# Page_A_Power.net
KiCad netlist of a schematic drawn in Altium Designer
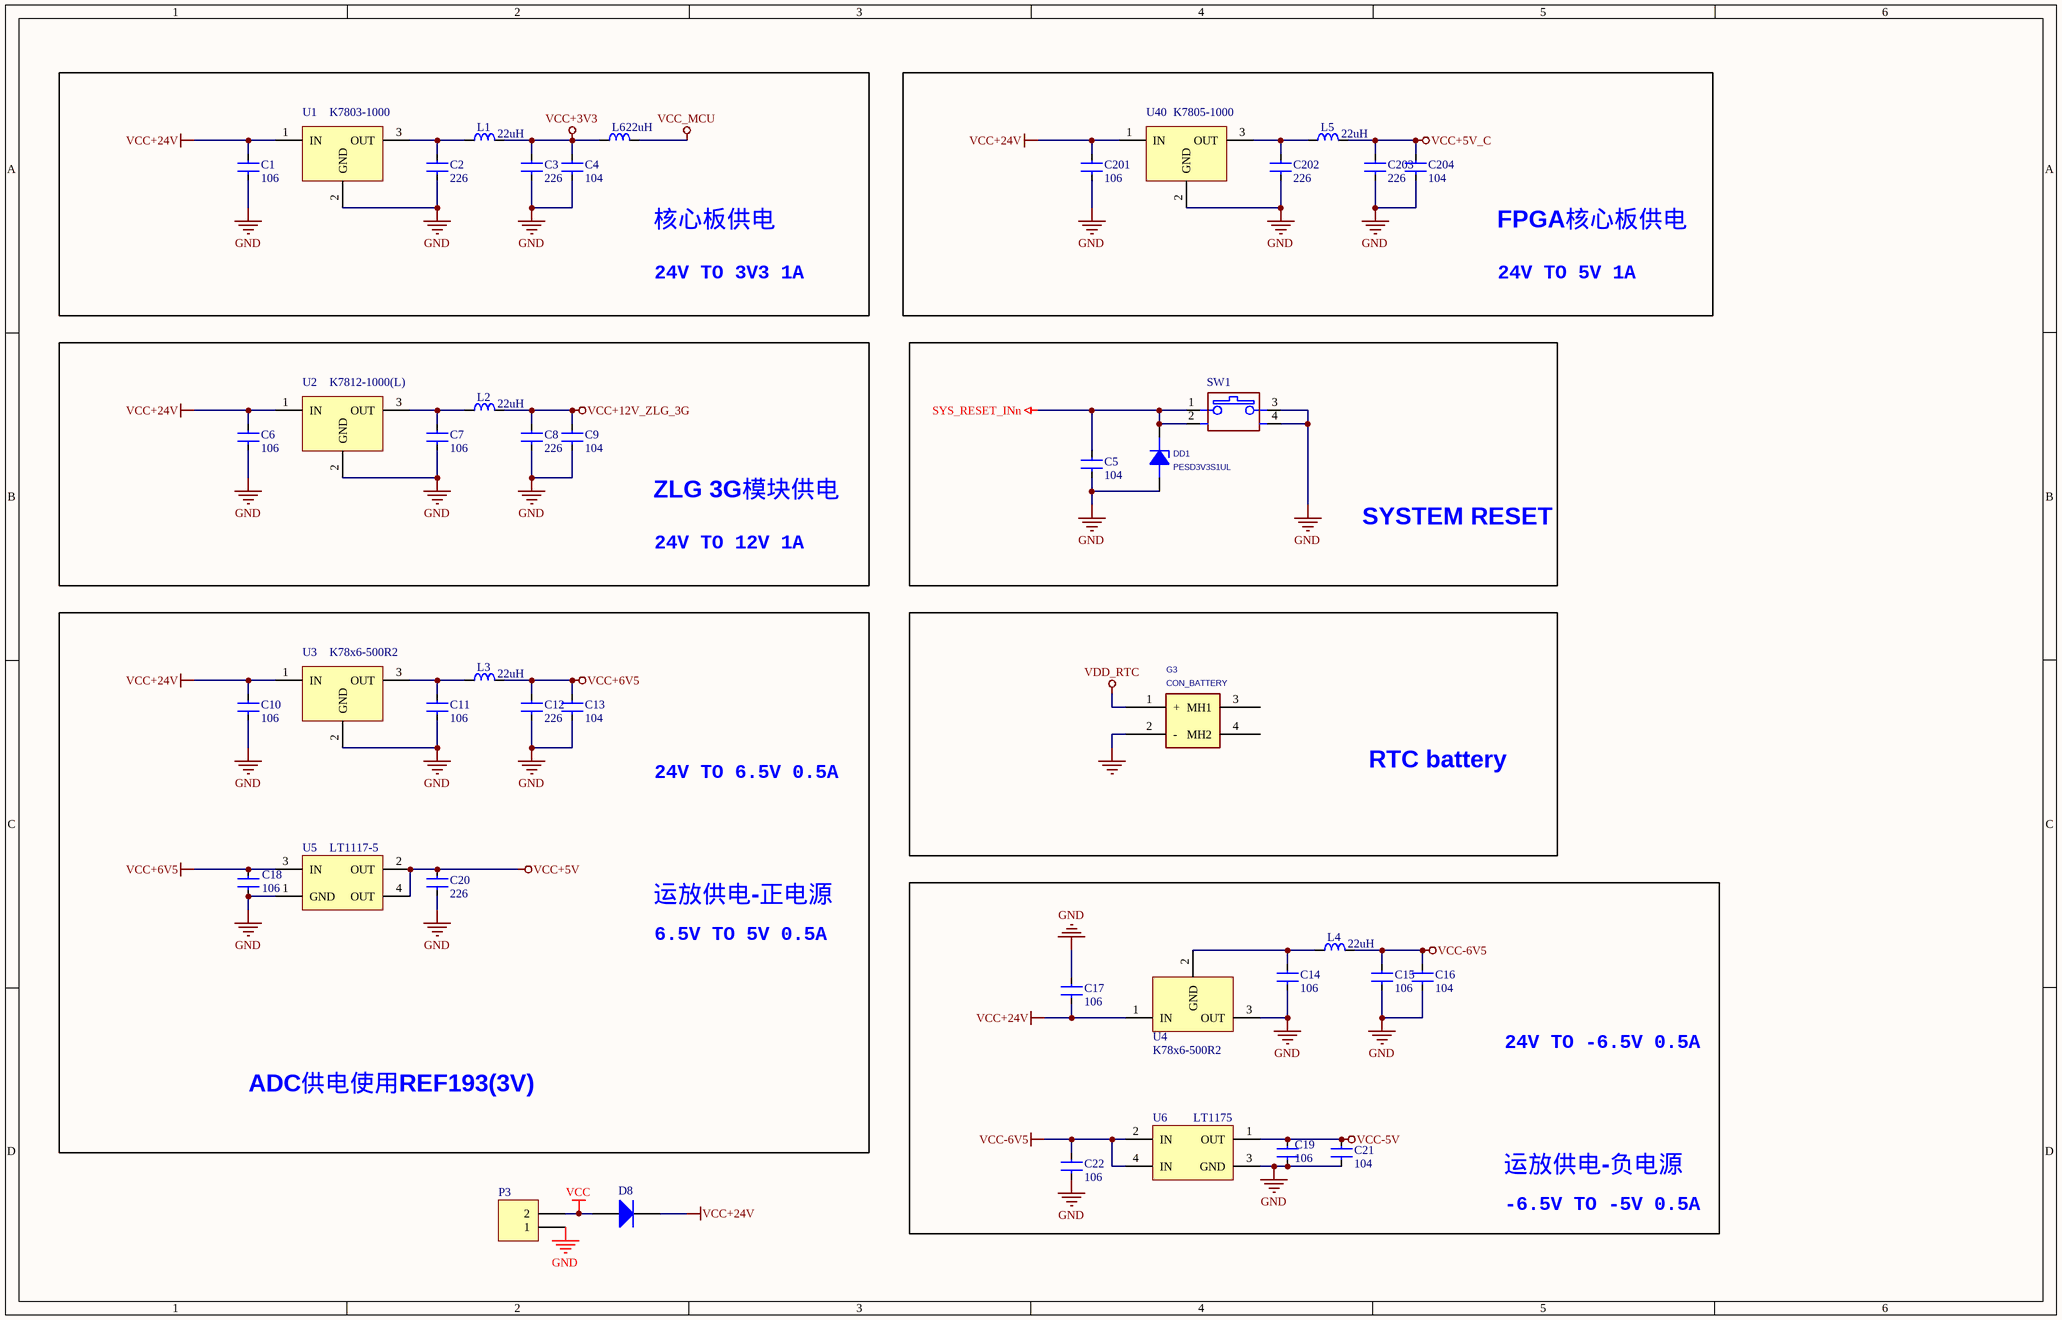
[diagram p0: Page A_Power.SchDoc]

(export (version "E")
  (design (tool "Eeschema 10.0.6"))
  (components
    (comp (ref "C1")
      (value "106")
      (footprint "0805C")
      (description "SMD")
      (libsource (lib "无极性电容") (part "C-SMD"))
    )
    (comp (ref "C2")
      (value "226")
      (footprint "0805C")
      (description "SMD")
      (libsource (lib "无极性电容") (part "C-SMD"))
    )
    (comp (ref "C3")
      (value "226")
      (footprint "0805C")
      (description "SMD")
      (libsource (lib "无极性电容") (part "C-SMD"))
    )
    (comp (ref "C4")
      (value "104")
      (footprint "0805C")
      (description "SMD")
      (libsource (lib "无极性电容") (part "C-SMD"))
    )
    (comp (ref "C5")
      (value "104")
      (footprint "0805C")
      (description "SMD")
      (libsource (lib "无极性电容") (part "C-SMD"))
    )
    (comp (ref "C6")
      (value "106")
      (footprint "0805C")
      (description "SMD")
      (libsource (lib "无极性电容") (part "C-SMD"))
    )
    (comp (ref "C7")
      (value "106")
      (footprint "0805C")
      (description "SMD")
      (libsource (lib "无极性电容") (part "C-SMD"))
    )
    (comp (ref "C8")
      (value "226")
      (footprint "0805C")
      (description "SMD")
      (libsource (lib "无极性电容") (part "C-SMD"))
    )
    (comp (ref "C9")
      (value "104")
      (footprint "0805C")
      (description "SMD")
      (libsource (lib "无极性电容") (part "C-SMD"))
    )
    (comp (ref "C10")
      (value "106")
      (footprint "0805C")
      (description "SMD")
      (libsource (lib "无极性电容") (part "C-SMD"))
    )
    (comp (ref "C11")
      (value "106")
      (footprint "0805C")
      (description "SMD")
      (libsource (lib "无极性电容") (part "C-SMD"))
    )
    (comp (ref "C12")
      (value "226")
      (footprint "0805C")
      (description "SMD")
      (libsource (lib "无极性电容") (part "C-SMD"))
    )
    (comp (ref "C13")
      (value "104")
      (footprint "0805C")
      (description "SMD")
      (libsource (lib "无极性电容") (part "C-SMD"))
    )
    (comp (ref "C14")
      (value "106")
      (footprint "0805C")
      (description "SMD")
      (libsource (lib "无极性电容") (part "C-SMD"))
    )
    (comp (ref "C15")
      (value "106")
      (footprint "0805C")
      (description "SMD")
      (libsource (lib "无极性电容") (part "C-SMD"))
    )
    (comp (ref "C16")
      (value "104")
      (footprint "0805C")
      (description "SMD")
      (libsource (lib "无极性电容") (part "C-SMD"))
    )
    (comp (ref "C17")
      (value "106")
      (footprint "0805C")
      (description "SMD")
      (libsource (lib "无极性电容") (part "C-SMD"))
    )
    (comp (ref "C18")
      (value "106")
      (footprint "0805C")
      (description "SMD")
      (libsource (lib "无极性电容") (part "C-SMD"))
    )
    (comp (ref "C19")
      (value "106")
      (footprint "0805C")
      (description "C-X5R/X7R")
      (libsource (lib "贴片电阻电容") (part "C-X5R/X7R"))
    )
    (comp (ref "C20")
      (value "226")
      (footprint "0805C")
      (description "SMD")
      (libsource (lib "无极性电容") (part "C-SMD"))
    )
    (comp (ref "C21")
      (value "104")
      (footprint "0805C")
      (description "C-X5R/X7R")
      (libsource (lib "贴片电阻电容") (part "C-X5R/X7R"))
    )
    (comp (ref "C22")
      (value "106")
      (footprint "0805C")
      (description "C-X5R/X7R")
      (libsource (lib "贴片电阻电容") (part "C-X5R/X7R"))
    )
    (comp (ref "C201")
      (value "106")
      (footprint "0805C")
      (description "SMD")
      (libsource (lib "无极性电容") (part "C-SMD"))
    )
    (comp (ref "C202")
      (value "226")
      (footprint "0805C")
      (description "SMD")
      (libsource (lib "无极性电容") (part "C-SMD"))
    )
    (comp (ref "C203")
      (value "226")
      (footprint "0805C")
      (description "SMD")
      (libsource (lib "无极性电容") (part "C-SMD"))
    )
    (comp (ref "C204")
      (value "104")
      (footprint "0805C")
      (description "SMD")
      (libsource (lib "无极性电容") (part "C-SMD"))
    )
    (comp (ref "D8")
      (value "1N4007")
      (footprint "DO-41")
      (description "High Conductance Fast Diode")
      (fields (field (name "PUBLISHER") "Altium Limited"))
      (libsource (lib "Miscellaneous Devices") (part "Diode 1N4148"))
    )
    (comp (ref "DD1")
      (value "PESD3V3S1UL")
      (footprint "SOD882")
      (fields (field (name "MANUFACTURER") "NXP"))
      (libsource (lib "*") (part "DIODE BREAKDOWN"))
    )
    (comp (ref "G3")
      (value "CON_BATTERY")
      (footprint "CON_BATTERY_CR1220")
      (libsource (lib "*") (part "CON_BATTERY"))
    )
    (comp (ref "L1")
      (value "22uH")
      (footprint "1210")
      (description "Inductor")
      (fields
        (field (name "PART NUMBER") "IND0603_TDK_MPZ1608R391A")
        (field (name "POWER") "1.2A")
        (field (name "AUTHOR") "CERN DEM JLC")
      )
      (libsource (lib "电感、变压器件") (part "Inductor"))
    )
    (comp (ref "L2")
      (value "22uH")
      (footprint "1210")
      (description "Inductor")
      (fields
        (field (name "PART NUMBER") "IND0603_TDK_MPZ1608R391A")
        (field (name "POWER") "1.2A")
        (field (name "AUTHOR") "CERN DEM JLC")
      )
      (libsource (lib "电感、变压器件") (part "Inductor"))
    )
    (comp (ref "L3")
      (value "22uH")
      (footprint "1210")
      (description "Inductor")
      (fields
        (field (name "PART NUMBER") "IND0603_TDK_MPZ1608R391A")
        (field (name "POWER") "1.2A")
        (field (name "AUTHOR") "CERN DEM JLC")
      )
      (libsource (lib "电感、变压器件") (part "Inductor"))
    )
    (comp (ref "L4")
      (value "22uH")
      (footprint "1210")
      (description "Inductor")
      (fields
        (field (name "PART NUMBER") "IND0603_TDK_MPZ1608R391A")
        (field (name "POWER") "1.2A")
        (field (name "AUTHOR") "CERN DEM JLC")
      )
      (libsource (lib "电感、变压器件") (part "Inductor"))
    )
    (comp (ref "L5")
      (value "22uH")
      (footprint "1210")
      (description "Inductor")
      (fields
        (field (name "PART NUMBER") "IND0603_TDK_MPZ1608R391A")
        (field (name "POWER") "1.2A")
        (field (name "AUTHOR") "CERN DEM JLC")
      )
      (libsource (lib "电感、变压器件") (part "Inductor"))
    )
    (comp (ref "L6")
      (value "22uH")
      (footprint "1210")
      (description "Inductor")
      (fields
        (field (name "PART NUMBER") "IND0603_TDK_MPZ1608R391A")
        (field (name "POWER") "1.2A")
        (field (name "AUTHOR") "CERN DEM JLC")
      )
      (libsource (lib "电感、变压器件") (part "Inductor"))
    )
    (comp (ref "P3")
      (value "Header 2")
      (footprint "7.62-2P")
      (description "Header, 2-Pin")
      (fields (field (name "PUBLISHER") "Altium Limited"))
      (libsource (lib "Miscellaneous Connectors") (part "Header 2"))
    )
    (comp (ref "SW1")
      (value "SW PUSHBUTTON-SPST SHIELD_0")
      (footprint "BUTTON_SW_SMD_4P_BIG")
      (libsource (lib "TL138_1808_6748F-EASYEVM-A2_Library") (part "SW PUSHBUTTON-SPST SHIELD_0"))
    )
    (comp (ref "U1")
      (value "K7803-1000")
      (footprint "K78xx-500R2")
      (description "K78xx-500R2")
      (libsource (lib "其他元器件") (part "K78xx-500R2"))
    )
    (comp (ref "U2")
      (value "K7812-1000(L)")
      (footprint "K78xx-L")
      (description "K78xx-500R2")
      (libsource (lib "其他元器件") (part "K78xx-500R2"))
    )
    (comp (ref "U3")
      (value "K78x6-500R2")
      (footprint "K78xx-500R2")
      (description "K78xx-500R2")
      (libsource (lib "其他元器件") (part "K78xx-500R2"))
    )
    (comp (ref "U4")
      (value "K78x6-500R2")
      (footprint "K78xx-500R2")
      (description "K78xx-500R2")
      (libsource (lib "") (part "K78xx-500R2_1"))
    )
    (comp (ref "U5")
      (value "LT1117-5")
      (footprint "SOT-223")
      (description "AMS1117")
      (libsource (lib "其他元器件") (part "AMS1117"))
    )
    (comp (ref "U6") (value "LT1175") (footprint "SOT-223") (libsource (lib "其他元器件") (part "LT1175")))
    (comp (ref "U40")
      (value "K7805-1000")
      (footprint "K78xx-500R2")
      (description "K78xx-500R2")
      (libsource (lib "其他元器件") (part "K78xx-500R2"))
    )
  )
  (nets
    (net (code "1") (name "GND") (class "Default")
      (node (ref "C1") (pin "2") (pinfunction "2_2") (pintype "passive"))
      (node (ref "C10") (pin "2") (pinfunction "2_2") (pintype "passive"))
      (node (ref "C11") (pin "2") (pinfunction "2_2") (pintype "passive"))
      (node (ref "C12") (pin "2") (pinfunction "2_2") (pintype "passive"))
      (node (ref "C13") (pin "2") (pinfunction "2_2") (pintype "passive"))
      (node (ref "C14") (pin "2") (pinfunction "2_2") (pintype "passive"))
      (node (ref "C15") (pin "2") (pinfunction "2_2") (pintype "passive"))
      (node (ref "C16") (pin "2") (pinfunction "2_2") (pintype "passive"))
      (node (ref "C17") (pin "2") (pinfunction "2_2") (pintype "passive"))
      (node (ref "C18") (pin "2") (pinfunction "2_2") (pintype "passive"))
      (node (ref "C19") (pin "2") (pinfunction "2_2") (pintype "passive"))
      (node (ref "C2") (pin "2") (pinfunction "2_2") (pintype "passive"))
      (node (ref "C20") (pin "2") (pinfunction "2_2") (pintype "passive"))
      (node (ref "C201") (pin "2") (pinfunction "2_2") (pintype "passive"))
      (node (ref "C202") (pin "2") (pinfunction "2_2") (pintype "passive"))
      (node (ref "C203") (pin "2") (pinfunction "2_2") (pintype "passive"))
      (node (ref "C204") (pin "2") (pinfunction "2_2") (pintype "passive"))
      (node (ref "C21") (pin "2") (pinfunction "2_2") (pintype "passive"))
      (node (ref "C22") (pin "2") (pinfunction "2_2") (pintype "passive"))
      (node (ref "C3") (pin "2") (pinfunction "2_2") (pintype "passive"))
      (node (ref "C4") (pin "2") (pinfunction "2_2") (pintype "passive"))
      (node (ref "C5") (pin "2") (pinfunction "2_2") (pintype "passive"))
      (node (ref "C6") (pin "2") (pinfunction "2_2") (pintype "passive"))
      (node (ref "C7") (pin "2") (pinfunction "2_2") (pintype "passive"))
      (node (ref "C8") (pin "2") (pinfunction "2_2") (pintype "passive"))
      (node (ref "C9") (pin "2") (pinfunction "2_2") (pintype "passive"))
      (node (ref "DD1") (pin "2") (pinfunction "ANODE_2") (pintype "passive"))
      (node (ref "G3") (pin "2") (pinfunction "-_2") (pintype "passive"))
      (node (ref "P3") (pin "1") (pinfunction "1_1") (pintype "passive"))
      (node (ref "SW1") (pin "3") (pinfunction "3_3") (pintype "passive"))
      (node (ref "SW1") (pin "4") (pinfunction "4_4") (pintype "passive"))
      (node (ref "U1") (pin "2") (pinfunction "GND_2") (pintype "passive"))
      (node (ref "U2") (pin "2") (pinfunction "GND_2") (pintype "passive"))
      (node (ref "U3") (pin "2") (pinfunction "GND_2") (pintype "passive"))
      (node (ref "U4") (pin "3") (pinfunction "OUT_3") (pintype "passive"))
      (node (ref "U40") (pin "2") (pinfunction "GND_2") (pintype "passive"))
      (node (ref "U5") (pin "1") (pinfunction "GND_1") (pintype "passive"))
      (node (ref "U6") (pin "3") (pinfunction "GND_3") (pintype "passive"))
    )
    (net (code "2") (name "Net-(U1-OUT)") (class "Default")
      (node (ref "C2") (pin "1") (pinfunction "1_1") (pintype "passive"))
      (node (ref "L1") (pin "1") (pinfunction "1_1") (pintype "passive"))
      (node (ref "U1") (pin "3") (pinfunction "OUT_3") (pintype "passive"))
    )
    (net (code "3") (name "Net-(U2-OUT)") (class "Default")
      (node (ref "C7") (pin "1") (pinfunction "1_1") (pintype "passive"))
      (node (ref "L2") (pin "1") (pinfunction "1_1") (pintype "passive"))
      (node (ref "U2") (pin "3") (pinfunction "OUT_3") (pintype "passive"))
    )
    (net (code "4") (name "Net-(U3-OUT)") (class "Default")
      (node (ref "C11") (pin "1") (pinfunction "1_1") (pintype "passive"))
      (node (ref "L3") (pin "1") (pinfunction "1_1") (pintype "passive"))
      (node (ref "U3") (pin "3") (pinfunction "OUT_3") (pintype "passive"))
    )
    (net (code "5") (name "Net-(U4-GND)") (class "Default")
      (node (ref "C14") (pin "1") (pinfunction "1_1") (pintype "passive"))
      (node (ref "L4") (pin "1") (pinfunction "1_1") (pintype "passive"))
      (node (ref "U4") (pin "2") (pinfunction "GND_2") (pintype "passive"))
    )
    (net (code "6") (name "Net-(U40-OUT)") (class "Default")
      (node (ref "C202") (pin "1") (pinfunction "1_1") (pintype "passive"))
      (node (ref "L5") (pin "1") (pinfunction "1_1") (pintype "passive"))
      (node (ref "U40") (pin "3") (pinfunction "OUT_3") (pintype "passive"))
    )
    (net (code "7") (name "SYS_RESET_INn") (class "Default")
      (node (ref "C5") (pin "1") (pinfunction "1_1") (pintype "passive"))
      (node (ref "DD1") (pin "1") (pinfunction "CATHODE_1") (pintype "passive"))
      (node (ref "SW1") (pin "1") (pinfunction "1_1") (pintype "passive"))
      (node (ref "SW1") (pin "2") (pinfunction "2_2") (pintype "passive"))
    )
    (net (code "8") (name "VCC") (class "Default")
      (node (ref "D8") (pin "1") (pinfunction "A_1") (pintype "passive"))
      (node (ref "P3") (pin "2") (pinfunction "2_2") (pintype "passive"))
    )
    (net (code "9") (name "VCC+3V3") (class "Default")
      (node (ref "C3") (pin "1") (pinfunction "1_1") (pintype "passive"))
      (node (ref "C4") (pin "1") (pinfunction "1_1") (pintype "passive"))
      (node (ref "L1") (pin "2") (pinfunction "2_2") (pintype "passive"))
      (node (ref "L6") (pin "1") (pinfunction "1_1") (pintype "passive"))
    )
    (net (code "10") (name "VCC+5V") (class "Default")
      (node (ref "C20") (pin "1") (pinfunction "1_1") (pintype "passive"))
      (node (ref "U5") (pin "2") (pinfunction "OUT_2") (pintype "passive"))
      (node (ref "U5") (pin "4") (pinfunction "OUT_4") (pintype "passive"))
    )
    (net (code "11") (name "VCC+5V_C") (class "Default")
      (node (ref "C203") (pin "1") (pinfunction "1_1") (pintype "passive"))
      (node (ref "C204") (pin "1") (pinfunction "1_1") (pintype "passive"))
      (node (ref "L5") (pin "2") (pinfunction "2_2") (pintype "passive"))
    )
    (net (code "12") (name "VCC+6V5") (class "Default")
      (node (ref "C12") (pin "1") (pinfunction "1_1") (pintype "passive"))
      (node (ref "C13") (pin "1") (pinfunction "1_1") (pintype "passive"))
      (node (ref "C18") (pin "1") (pinfunction "1_1") (pintype "passive"))
      (node (ref "L3") (pin "2") (pinfunction "2_2") (pintype "passive"))
      (node (ref "U5") (pin "3") (pinfunction "IN_3") (pintype "passive"))
    )
    (net (code "13") (name "VCC+12V_ZLG_3G") (class "Default")
      (node (ref "C8") (pin "1") (pinfunction "1_1") (pintype "passive"))
      (node (ref "C9") (pin "1") (pinfunction "1_1") (pintype "passive"))
      (node (ref "L2") (pin "2") (pinfunction "2_2") (pintype "passive"))
    )
    (net (code "14") (name "VCC+24V") (class "Default")
      (node (ref "C1") (pin "1") (pinfunction "1_1") (pintype "passive"))
      (node (ref "C10") (pin "1") (pinfunction "1_1") (pintype "passive"))
      (node (ref "C17") (pin "1") (pinfunction "1_1") (pintype "passive"))
      (node (ref "C201") (pin "1") (pinfunction "1_1") (pintype "passive"))
      (node (ref "C6") (pin "1") (pinfunction "1_1") (pintype "passive"))
      (node (ref "D8") (pin "2") (pinfunction "K_2") (pintype "passive"))
      (node (ref "U1") (pin "1") (pinfunction "IN_1") (pintype "passive"))
      (node (ref "U2") (pin "1") (pinfunction "IN_1") (pintype "passive"))
      (node (ref "U3") (pin "1") (pinfunction "IN_1") (pintype "passive"))
      (node (ref "U4") (pin "1") (pinfunction "IN_1") (pintype "passive"))
      (node (ref "U40") (pin "1") (pinfunction "IN_1") (pintype "passive"))
    )
    (net (code "15") (name "VCC-5V") (class "Default")
      (node (ref "C19") (pin "1") (pinfunction "1_1") (pintype "passive"))
      (node (ref "C21") (pin "1") (pinfunction "1_1") (pintype "passive"))
      (node (ref "U6") (pin "1") (pinfunction "OUT_1") (pintype "passive"))
    )
    (net (code "16") (name "VCC-6V5") (class "Default")
      (node (ref "C15") (pin "1") (pinfunction "1_1") (pintype "passive"))
      (node (ref "C16") (pin "1") (pinfunction "1_1") (pintype "passive"))
      (node (ref "C22") (pin "1") (pinfunction "1_1") (pintype "passive"))
      (node (ref "L4") (pin "2") (pinfunction "2_2") (pintype "passive"))
      (node (ref "U6") (pin "2") (pinfunction "IN_2") (pintype "passive"))
      (node (ref "U6") (pin "4") (pinfunction "IN_4") (pintype "passive"))
    )
    (net (code "17") (name "VCC_MCU") (class "Default")
      (node (ref "L6") (pin "2") (pinfunction "2_2") (pintype "passive"))
    )
    (net (code "18") (name "VDD_RTC") (class "Default")
      (node (ref "G3") (pin "1") (pinfunction "+_1") (pintype "passive"))
    )
    (net (code "19") (name "unconnected-(G3-MH1-Pad3)") (class "Default")
      (node (ref "G3") (pin "3") (pinfunction "MH1_3") (pintype "passive"))
    )
    (net (code "20") (name "unconnected-(G3-MH2-Pad4)") (class "Default")
      (node (ref "G3") (pin "4") (pinfunction "MH2_4") (pintype "passive"))
    )
  )
)
